# Drone_v1_0.net
KiCad netlist of a schematic drawn in Altium Designer
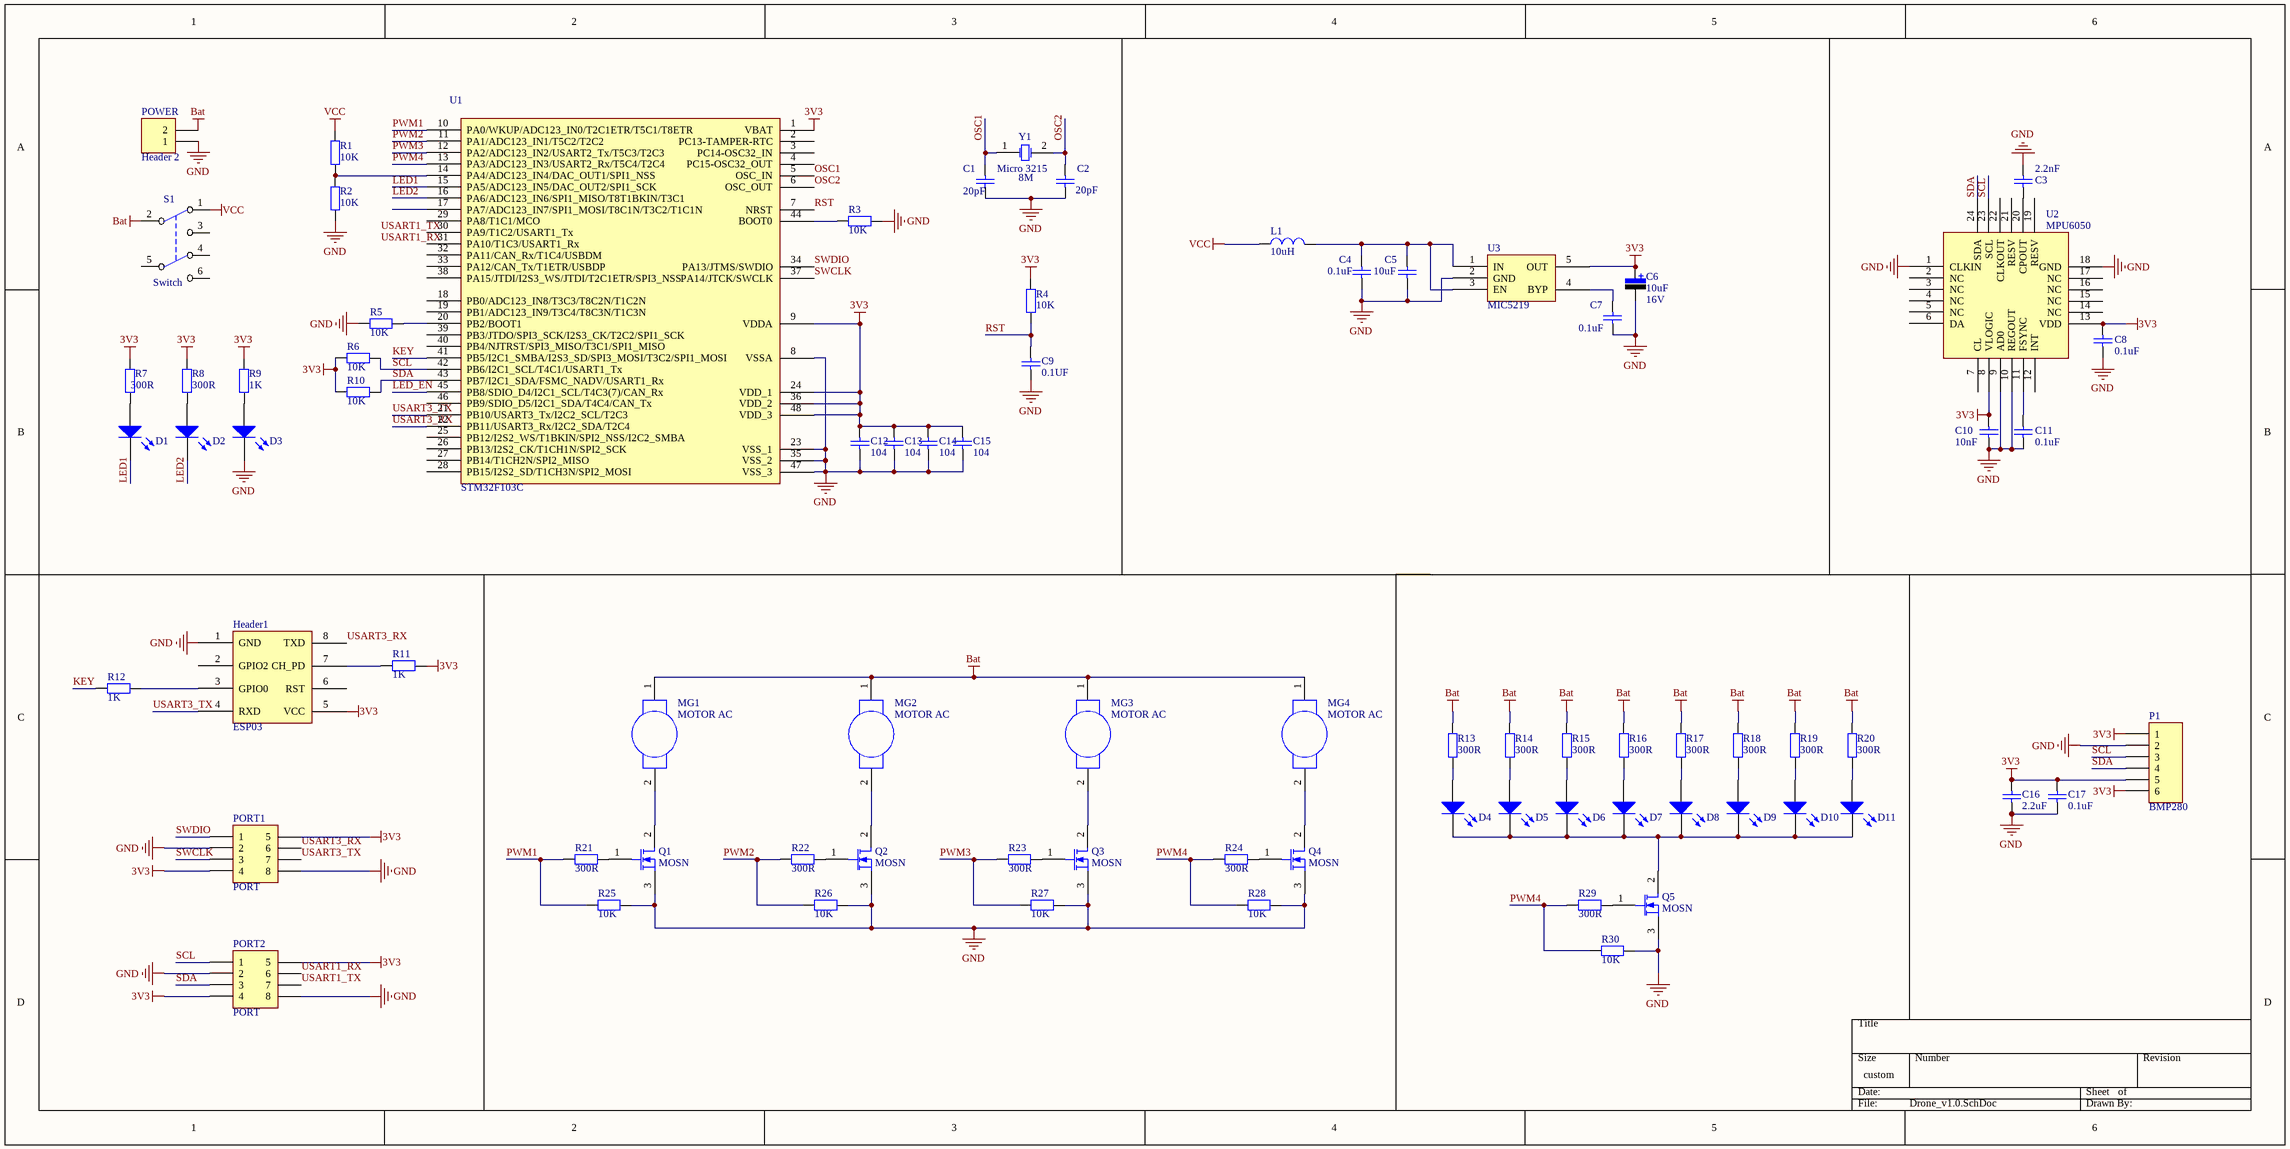
[diagram p0: Drone_v1.0.SchDoc]

(export (version "E")
  (design (tool "Eeschema 10.0.6"))
  (components
    (comp (ref "C1")
      (value "20pF")
      (footprint "0805-2")
      (description "Capacitor")
      (fields (field (name "Comment") "0402 12pF") (field (name "PUBLISHER") "Altium Limited"))
      (libsource (lib "Miscellaneous Devices") (part "Cap"))
    )
    (comp (ref "C2")
      (value "20pF")
      (footprint "0805-2")
      (description "Capacitor")
      (fields (field (name "Comment") "0402 12pF") (field (name "PUBLISHER") "Altium Limited"))
      (libsource (lib "Miscellaneous Devices") (part "Cap"))
    )
    (comp (ref "C3")
      (value "0402 12pF")
      (footprint "0805-2")
      (description "Capacitor")
      (fields (field (name "50V") "2.2nF") (field (name "PUBLISHER") "Altium Limited"))
      (libsource (lib "Miscellaneous Devices") (part "Cap"))
    )
    (comp (ref "C4")
      (value "0.1uF")
      (footprint "0805-2")
      (description "Capacitor")
      (fields (field (name "Comment") "0402 12pF") (field (name "PUBLISHER") "Altium Limited"))
      (libsource (lib "Miscellaneous Devices") (part "Cap"))
    )
    (comp (ref "C5")
      (value "10uF")
      (footprint "0805-2")
      (description "Capacitor")
      (fields (field (name "Comment") "0402 12pF") (field (name "PUBLISHER") "Altium Limited"))
      (libsource (lib "Miscellaneous Devices") (part "Cap"))
    )
    (comp (ref "C6")
      (value "10uF")
      (footprint "1206")
      (description "极性电解电容")
      (fields
        (field (name "VOL") "16V")
        (field (name "Comment") "Cap Pol")
        (field (name "PUBLISHER") "Altium Limited")
      )
      (libsource (lib "Fszhang") (part "Cap Pol"))
    )
    (comp (ref "C7")
      (value "0402 12pF")
      (footprint "0805-2")
      (description "Capacitor")
      (fields (field (name "50V") "0.1uF") (field (name "PUBLISHER") "Altium Limited"))
      (libsource (lib "Miscellaneous Devices") (part "Cap"))
    )
    (comp (ref "C8")
      (value "0402 12pF")
      (footprint "0805-2")
      (description "Capacitor")
      (fields (field (name "50V") "0.1uF") (field (name "PUBLISHER") "Altium Limited"))
      (libsource (lib "Miscellaneous Devices") (part "Cap"))
    )
    (comp (ref "C9")
      (value "0.1UF")
      (footprint "0805-2")
      (description "无极性电容")
      (fields (field (name "Comment") "Cap") (field (name "PUBLISHER") "Altium Limited"))
      (libsource (lib "Fszhang") (part "Cap"))
    )
    (comp (ref "C10")
      (value "0402 12pF")
      (footprint "0805-2")
      (description "Capacitor")
      (fields (field (name "50V") "10nF") (field (name "PUBLISHER") "Altium Limited"))
      (libsource (lib "Miscellaneous Devices") (part "Cap"))
    )
    (comp (ref "C11")
      (value "0402 12pF")
      (footprint "0805-2")
      (description "Capacitor")
      (fields (field (name "50V") "0.1uF") (field (name "PUBLISHER") "Altium Limited"))
      (libsource (lib "Miscellaneous Devices") (part "Cap"))
    )
    (comp (ref "C12")
      (value "104")
      (footprint "0805-2")
      (description "无极性电容")
      (fields (field (name "Comment") "Cap") (field (name "PUBLISHER") "Altium Limited"))
      (libsource (lib "Fszhang") (part "Cap"))
    )
    (comp (ref "C13")
      (value "104")
      (footprint "0805-2")
      (description "无极性电容")
      (fields (field (name "Comment") "Cap") (field (name "PUBLISHER") "Altium Limited"))
      (libsource (lib "Fszhang") (part "Cap"))
    )
    (comp (ref "C14")
      (value "104")
      (footprint "0805-2")
      (description "无极性电容")
      (fields (field (name "Comment") "Cap") (field (name "PUBLISHER") "Altium Limited"))
      (libsource (lib "Fszhang") (part "Cap"))
    )
    (comp (ref "C15")
      (value "104")
      (footprint "0805-2")
      (description "无极性电容")
      (fields (field (name "Comment") "Cap") (field (name "PUBLISHER") "Altium Limited"))
      (libsource (lib "Fszhang") (part "Cap"))
    )
    (comp (ref "C16")
      (value "0402 12pF")
      (footprint "0805-2")
      (description "Capacitor")
      (fields (field (name "50V") "2.2uF") (field (name "PUBLISHER") "Altium Limited"))
      (libsource (lib "Miscellaneous Devices") (part "Cap"))
    )
    (comp (ref "C17")
      (value "0402 12pF")
      (footprint "0805-2")
      (description "Capacitor")
      (fields (field (name "50V") "0.1uF") (field (name "PUBLISHER") "Altium Limited"))
      (libsource (lib "Miscellaneous Devices") (part "Cap"))
    )
    (comp (ref "D1")
      (value "LED0")
      (footprint "LED_0805")
      (description "发光二极管")
      (fields (field (name "PUBLISHER") "Altium Limited"))
      (libsource (lib "Fszhang") (part "LED0"))
    )
    (comp (ref "D2")
      (value "LED0")
      (footprint "LED_0805")
      (description "发光二极管")
      (fields (field (name "PUBLISHER") "Altium Limited"))
      (libsource (lib "Fszhang") (part "LED0"))
    )
    (comp (ref "D3")
      (value "LED0")
      (footprint "LED_0805")
      (description "发光二极管")
      (fields (field (name "PUBLISHER") "Altium Limited"))
      (libsource (lib "Fszhang") (part "LED0"))
    )
    (comp (ref "D4")
      (value "LED0")
      (footprint "LED_0805")
      (description "发光二极管")
      (fields (field (name "PUBLISHER") "Altium Limited"))
      (libsource (lib "Fszhang") (part "LED0"))
    )
    (comp (ref "D5")
      (value "LED0")
      (footprint "LED_0805")
      (description "发光二极管")
      (fields (field (name "PUBLISHER") "Altium Limited"))
      (libsource (lib "Fszhang") (part "LED0"))
    )
    (comp (ref "D6")
      (value "LED0")
      (footprint "LED_0805")
      (description "发光二极管")
      (fields (field (name "PUBLISHER") "Altium Limited"))
      (libsource (lib "Fszhang") (part "LED0"))
    )
    (comp (ref "D7")
      (value "LED0")
      (footprint "LED_0805")
      (description "发光二极管")
      (fields (field (name "PUBLISHER") "Altium Limited"))
      (libsource (lib "Fszhang") (part "LED0"))
    )
    (comp (ref "D8")
      (value "LED0")
      (footprint "LED_0805")
      (description "发光二极管")
      (fields (field (name "PUBLISHER") "Altium Limited"))
      (libsource (lib "Fszhang") (part "LED0"))
    )
    (comp (ref "D9")
      (value "LED0")
      (footprint "LED_0805")
      (description "发光二极管")
      (fields (field (name "PUBLISHER") "Altium Limited"))
      (libsource (lib "Fszhang") (part "LED0"))
    )
    (comp (ref "D10")
      (value "LED0")
      (footprint "LED_0805")
      (description "发光二极管")
      (fields (field (name "PUBLISHER") "Altium Limited"))
      (libsource (lib "Fszhang") (part "LED0"))
    )
    (comp (ref "D11")
      (value "LED0")
      (footprint "LED_0805")
      (description "发光二极管")
      (fields (field (name "PUBLISHER") "Altium Limited"))
      (libsource (lib "Fszhang") (part "LED0"))
    )
    (comp (ref "Header1")
      (value "ESP03")
      (footprint "PCBComponent_1")
      (libsource (lib "Header4") (part "Hearder"))
    )
    (comp (ref "L1")
      (value "10uH")
      (footprint "0805-1")
      (description "电感")
      (fields (field (name "Comment") "Inductor") (field (name "PUBLISHER") "Altium Limited"))
      (libsource (lib "Fszhang") (part "Inductor"))
    )
    (comp (ref "MG1") (value "MOTOR AC") (footprint "Motor") (libsource (lib "杂元件库") (part "MOTOR AC")))
    (comp (ref "MG2") (value "MOTOR AC") (footprint "Motor") (libsource (lib "杂元件库") (part "MOTOR AC")))
    (comp (ref "MG3") (value "MOTOR AC") (footprint "Motor") (libsource (lib "杂元件库") (part "MOTOR AC")))
    (comp (ref "MG4") (value "MOTOR AC") (footprint "Motor") (libsource (lib "杂元件库") (part "MOTOR AC")))
    (comp (ref "P1")
      (value "BMP280")
      (footprint "HDR1X6")
      (description "Header, 6-Pin")
      (fields (field (name "PUBLISHER") "Altium Limited"))
      (libsource (lib "Miscellaneous Connectors") (part "Header 6"))
    )
    (comp (ref "PORT1")
      (value "PORT")
      (footprint "HDR2X4_CEN")
      (description "Header, 4-Pin, Dual row")
      (fields (field (name "PUBLISHER") "Altium Limited"))
      (libsource (lib "Miscellaneous Connectors") (part "Header 4X2A"))
    )
    (comp (ref "PORT2")
      (value "PORT")
      (footprint "HDR2X4_CEN")
      (description "Header, 4-Pin, Dual row")
      (fields (field (name "PUBLISHER") "Altium Limited"))
      (libsource (lib "Miscellaneous Connectors") (part "Header 4X2A"))
    )
    (comp (ref "POWER")
      (value "Header 2")
      (footprint "HDR1X2")
      (description "Header, 2-Pin")
      (fields (field (name "PUBLISHER") "Altium Limited"))
      (libsource (lib "Miscellaneous Connectors") (part "Header 2"))
    )
    (comp (ref "Q1") (value "MOSN") (footprint "PCBComponent_1") (libsource (lib "MOS-N") (part "SI2302")))
    (comp (ref "Q2") (value "MOSN") (footprint "PCBComponent_1") (libsource (lib "MOS-N") (part "SI2302")))
    (comp (ref "Q3") (value "MOSN") (footprint "PCBComponent_1") (libsource (lib "MOS-N") (part "SI2302")))
    (comp (ref "Q4") (value "MOSN") (footprint "PCBComponent_1") (libsource (lib "MOS-N") (part "SI2302")))
    (comp (ref "Q5") (value "MOSN") (footprint "PCBComponent_1") (libsource (lib "MOS-N") (part "SI2302")))
    (comp (ref "R1")
      (value "10K")
      (footprint "0805-2")
      (description "贴片电阻")
      (fields (field (name "Comment") "Res1") (field (name "PUBLISHER") "Altium Limited"))
      (libsource (lib "") (part "Res1_2"))
    )
    (comp (ref "R2")
      (value "10K")
      (footprint "0805-2")
      (description "贴片电阻")
      (fields (field (name "Comment") "Res1") (field (name "PUBLISHER") "Altium Limited"))
      (libsource (lib "") (part "Res1_1"))
    )
    (comp (ref "R3")
      (value "10K")
      (footprint "0805-2")
      (description "贴片电阻")
      (fields (field (name "Comment") "Res1") (field (name "PUBLISHER") "Altium Limited"))
      (libsource (lib "Fszhang") (part "Res1"))
    )
    (comp (ref "R4")
      (value "10K")
      (footprint "0805-2")
      (description "贴片电阻")
      (fields (field (name "Comment") "Res1") (field (name "PUBLISHER") "Altium Limited"))
      (libsource (lib "") (part "Res1_2"))
    )
    (comp (ref "R5")
      (value "10K")
      (footprint "0805-2")
      (description "贴片电阻")
      (fields (field (name "Comment") "Res1") (field (name "PUBLISHER") "Altium Limited"))
      (libsource (lib "") (part "Res1_3"))
    )
    (comp (ref "R6")
      (value "10K")
      (footprint "0805-2")
      (description "贴片电阻")
      (fields (field (name "Comment") "Res1") (field (name "PUBLISHER") "Altium Limited"))
      (libsource (lib "") (part "Res1_3"))
    )
    (comp (ref "R7")
      (value "300R")
      (footprint "0805-2")
      (description "贴片电阻")
      (fields (field (name "Comment") "Res1") (field (name "PUBLISHER") "Altium Limited"))
      (libsource (lib "") (part "Res1_2"))
    )
    (comp (ref "R8")
      (value "300R")
      (footprint "0805-2")
      (description "贴片电阻")
      (fields (field (name "Comment") "Res1") (field (name "PUBLISHER") "Altium Limited"))
      (libsource (lib "") (part "Res1_2"))
    )
    (comp (ref "R9")
      (value "1K")
      (footprint "0805-2")
      (description "贴片电阻")
      (fields (field (name "Comment") "Res1") (field (name "PUBLISHER") "Altium Limited"))
      (libsource (lib "") (part "Res1_2"))
    )
    (comp (ref "R10")
      (value "10K")
      (footprint "0805-2")
      (description "贴片电阻")
      (fields (field (name "Comment") "Res1") (field (name "PUBLISHER") "Altium Limited"))
      (libsource (lib "") (part "Res1_3"))
    )
    (comp (ref "R11")
      (value "1K")
      (footprint "0805-2")
      (description "贴片电阻")
      (fields (field (name "Comment") "Res1") (field (name "PUBLISHER") "Altium Limited"))
      (libsource (lib "") (part "Res1_3"))
    )
    (comp (ref "R12")
      (value "1K")
      (footprint "0805-2")
      (description "贴片电阻")
      (fields (field (name "Comment") "Res1") (field (name "PUBLISHER") "Altium Limited"))
      (libsource (lib "") (part "Res1_3"))
    )
    (comp (ref "R13")
      (value "300R")
      (footprint "0805-2")
      (description "贴片电阻")
      (fields (field (name "Comment") "Res1") (field (name "PUBLISHER") "Altium Limited"))
      (libsource (lib "") (part "Res1_1"))
    )
    (comp (ref "R14")
      (value "300R")
      (footprint "0805-2")
      (description "贴片电阻")
      (fields (field (name "Comment") "Res1") (field (name "PUBLISHER") "Altium Limited"))
      (libsource (lib "") (part "Res1_1"))
    )
    (comp (ref "R15")
      (value "300R")
      (footprint "0805-2")
      (description "贴片电阻")
      (fields (field (name "Comment") "Res1") (field (name "PUBLISHER") "Altium Limited"))
      (libsource (lib "") (part "Res1_1"))
    )
    (comp (ref "R16")
      (value "300R")
      (footprint "0805-2")
      (description "贴片电阻")
      (fields (field (name "Comment") "Res1") (field (name "PUBLISHER") "Altium Limited"))
      (libsource (lib "") (part "Res1_1"))
    )
    (comp (ref "R17")
      (value "300R")
      (footprint "0805-2")
      (description "贴片电阻")
      (fields (field (name "Comment") "Res1") (field (name "PUBLISHER") "Altium Limited"))
      (libsource (lib "") (part "Res1_1"))
    )
    (comp (ref "R18")
      (value "300R")
      (footprint "0805-2")
      (description "贴片电阻")
      (fields (field (name "Comment") "Res1") (field (name "PUBLISHER") "Altium Limited"))
      (libsource (lib "") (part "Res1_1"))
    )
    (comp (ref "R19")
      (value "300R")
      (footprint "0805-2")
      (description "贴片电阻")
      (fields (field (name "Comment") "Res1") (field (name "PUBLISHER") "Altium Limited"))
      (libsource (lib "") (part "Res1_1"))
    )
    (comp (ref "R20")
      (value "300R")
      (footprint "0805-2")
      (description "贴片电阻")
      (fields (field (name "Comment") "Res1") (field (name "PUBLISHER") "Altium Limited"))
      (libsource (lib "") (part "Res1_1"))
    )
    (comp (ref "R21")
      (value "300R")
      (footprint "0805-2")
      (description "贴片电阻")
      (fields (field (name "Comment") "Res1") (field (name "PUBLISHER") "Altium Limited"))
      (libsource (lib "Fszhang") (part "Res1"))
    )
    (comp (ref "R22")
      (value "300R")
      (footprint "0805-2")
      (description "贴片电阻")
      (fields (field (name "Comment") "Res1") (field (name "PUBLISHER") "Altium Limited"))
      (libsource (lib "Fszhang") (part "Res1"))
    )
    (comp (ref "R23")
      (value "300R")
      (footprint "0805-2")
      (description "贴片电阻")
      (fields (field (name "Comment") "Res1") (field (name "PUBLISHER") "Altium Limited"))
      (libsource (lib "Fszhang") (part "Res1"))
    )
    (comp (ref "R24")
      (value "300R")
      (footprint "0805-2")
      (description "贴片电阻")
      (fields (field (name "Comment") "Res1") (field (name "PUBLISHER") "Altium Limited"))
      (libsource (lib "Fszhang") (part "Res1"))
    )
    (comp (ref "R25")
      (value "10K")
      (footprint "0805-2")
      (description "贴片电阻")
      (fields (field (name "Comment") "Res1") (field (name "PUBLISHER") "Altium Limited"))
      (libsource (lib "Fszhang") (part "Res1"))
    )
    (comp (ref "R26")
      (value "10K")
      (footprint "0805-2")
      (description "贴片电阻")
      (fields (field (name "Comment") "Res1") (field (name "PUBLISHER") "Altium Limited"))
      (libsource (lib "Fszhang") (part "Res1"))
    )
    (comp (ref "R27")
      (value "10K")
      (footprint "0805-2")
      (description "贴片电阻")
      (fields (field (name "Comment") "Res1") (field (name "PUBLISHER") "Altium Limited"))
      (libsource (lib "Fszhang") (part "Res1"))
    )
    (comp (ref "R28")
      (value "10K")
      (footprint "0805-2")
      (description "贴片电阻")
      (fields (field (name "Comment") "Res1") (field (name "PUBLISHER") "Altium Limited"))
      (libsource (lib "Fszhang") (part "Res1"))
    )
    (comp (ref "R29")
      (value "300R")
      (footprint "0805-2")
      (description "贴片电阻")
      (fields (field (name "Comment") "Res1") (field (name "PUBLISHER") "Altium Limited"))
      (libsource (lib "Fszhang") (part "Res1"))
    )
    (comp (ref "R30")
      (value "10K")
      (footprint "0805-2")
      (description "贴片电阻")
      (fields (field (name "Comment") "Res1") (field (name "PUBLISHER") "Altium Limited"))
      (libsource (lib "Fszhang") (part "Res1"))
    )
    (comp (ref "S1") (value "Switch") (footprint "开关") (libsource (lib "开关") (part "双刀双柄开关")))
    (comp (ref "U1")
      (value "STM32F103C")
      (footprint "LQFP-48_M")
      (description "STM32单片机48引脚")
      (libsource (lib "Fszhang") (part "STM32F103C"))
    )
    (comp (ref "U2")
      (value "MPU6050")
      (footprint "QFN50P400X400X90-24N")
      (libsource (lib "MPU6050") (part "MPU6050"))
    )
    (comp (ref "U3") (value "MIC5219") (footprint "SOT25-5") (libsource (lib "MIC5219") (part "MIC5219")))
    (comp (ref "Y1")
      (value "Micro 3215")
      (footprint "XTAL5")
      (description "Crystal Oscillator")
      (fields (field (name "ALTIUM_VALUE") "8M"))
      (libsource (lib "Miscellaneous Devices") (part "XTAL"))
    )
  )
  (nets
    (net (code "1") (name "/KEY") (class "Default")
      (node (ref "R12") (pin "1") (pinfunction "1_1") (pintype "passive"))
      (node (ref "U1") (pin "41") (pinfunction "PB5/I2C1_SMBA/I2S3_SD/SPI3_MOSI/T3C2/SPI1_MOSI_41") (pintype "passive"))
    )
    (net (code "2") (name "/LED1") (class "Default")
      (node (ref "D1") (pin "2") (pinfunction "K_2") (pintype "passive"))
      (node (ref "U1") (pin "15") (pinfunction "PA5/ADC123_IN5/DAC_OUT2/SPI1_SCK_15") (pintype "passive"))
    )
    (net (code "3") (name "/LED2") (class "Default")
      (node (ref "D2") (pin "2") (pinfunction "K_2") (pintype "passive"))
      (node (ref "U1") (pin "16") (pinfunction "PA6/ADC123_IN6/SPI1_MISO/T8T1BKIN/T3C1_16") (pintype "passive"))
    )
    (net (code "4") (name "/LED_EN") (class "Default")
      (node (ref "U1") (pin "45") (pinfunction "PB8/SDIO_D4/I2C1_SCL/T4C3(7)/CAN_Rx_45") (pintype "passive"))
    )
    (net (code "5") (name "/OSC1") (class "Default")
      (node (ref "C1") (pin "1") (pinfunction "1_1") (pintype "passive"))
      (node (ref "U1") (pin "5") (pinfunction "OSC_IN_5") (pintype "passive"))
      (node (ref "Y1") (pin "1") (pinfunction "OSC1_1") (pintype "passive"))
    )
    (net (code "6") (name "/OSC2") (class "Default")
      (node (ref "C2") (pin "2") (pinfunction "2_2") (pintype "passive"))
      (node (ref "U1") (pin "6") (pinfunction "OSC_OUT_6") (pintype "passive"))
      (node (ref "Y1") (pin "2") (pinfunction "OSC2_2") (pintype "passive"))
    )
    (net (code "7") (name "/PWM1") (class "Default")
      (node (ref "R21") (pin "2") (pinfunction "2_2") (pintype "passive"))
      (node (ref "R25") (pin "2") (pinfunction "2_2") (pintype "passive"))
      (node (ref "U1") (pin "10") (pinfunction "PA0/WKUP/ADC123_IN0/T2C1ETR/T5C1/T8ETR_10") (pintype "passive"))
    )
    (net (code "8") (name "/PWM2") (class "Default")
      (node (ref "R22") (pin "2") (pinfunction "2_2") (pintype "passive"))
      (node (ref "R26") (pin "2") (pinfunction "2_2") (pintype "passive"))
      (node (ref "U1") (pin "11") (pinfunction "PA1/ADC123_IN1/T5C2/T2C2_11") (pintype "passive"))
    )
    (net (code "9") (name "/PWM3") (class "Default")
      (node (ref "R23") (pin "2") (pinfunction "2_2") (pintype "passive"))
      (node (ref "R27") (pin "2") (pinfunction "2_2") (pintype "passive"))
      (node (ref "U1") (pin "12") (pinfunction "PA2/ADC123_IN2/USART2_Tx/T5C3/T2C3_12") (pintype "passive"))
    )
    (net (code "10") (name "/PWM4") (class "Default")
      (node (ref "R24") (pin "2") (pinfunction "2_2") (pintype "passive"))
      (node (ref "R28") (pin "2") (pinfunction "2_2") (pintype "passive"))
      (node (ref "R29") (pin "2") (pinfunction "2_2") (pintype "passive"))
      (node (ref "R30") (pin "2") (pinfunction "2_2") (pintype "passive"))
      (node (ref "U1") (pin "13") (pinfunction "PA3/ADC123_IN3/USART2_Rx/T5C4/T2C4_13") (pintype "passive"))
    )
    (net (code "11") (name "/RST") (class "Default")
      (node (ref "C9") (pin "1") (pinfunction "1_1") (pintype "passive"))
      (node (ref "R4") (pin "1") (pinfunction "1_1") (pintype "passive"))
      (node (ref "U1") (pin "7") (pinfunction "NRST_7") (pintype "passive"))
    )
    (net (code "12") (name "/SCL") (class "Default")
      (node (ref "P1") (pin "3") (pinfunction "3_3") (pintype "passive"))
      (node (ref "PORT2") (pin "1") (pinfunction "1_1") (pintype "passive"))
      (node (ref "R6") (pin "2") (pinfunction "2_2") (pintype "passive"))
      (node (ref "U1") (pin "42") (pinfunction "PB6/I2C1_SCL/T4C1/USART1_Tx_42") (pintype "passive"))
      (node (ref "U2") (pin "23") (pinfunction "SCL_23") (pintype "passive"))
    )
    (net (code "13") (name "/SDA") (class "Default")
      (node (ref "P1") (pin "4") (pinfunction "4_4") (pintype "passive"))
      (node (ref "PORT2") (pin "3") (pinfunction "3_3") (pintype "passive"))
      (node (ref "R10") (pin "2") (pinfunction "2_2") (pintype "passive"))
      (node (ref "U1") (pin "43") (pinfunction "PB7/I2C1_SDA/FSMC_NADV/USART1_Rx_43") (pintype "passive"))
      (node (ref "U2") (pin "24") (pinfunction "SDA_24") (pintype "passive"))
    )
    (net (code "14") (name "/SWCLK") (class "Default")
      (node (ref "PORT1") (pin "3") (pinfunction "3_3") (pintype "passive"))
      (node (ref "U1") (pin "37") (pinfunction "PA14/JTCK/SWCLK_37") (pintype "passive"))
    )
    (net (code "15") (name "/SWDIO") (class "Default")
      (node (ref "PORT1") (pin "1") (pinfunction "1_1") (pintype "passive"))
      (node (ref "U1") (pin "34") (pinfunction "PA13/JTMS/SWDIO_34") (pintype "passive"))
    )
    (net (code "16") (name "/USART1_RX") (class "Default")
      (node (ref "PORT2") (pin "6") (pinfunction "6_6") (pintype "passive"))
    )
    (net (code "17") (name "/USART1_TX") (class "Default")
      (node (ref "PORT2") (pin "7") (pinfunction "7_7") (pintype "passive"))
    )
    (net (code "18") (name "/USART3_RX") (class "Default")
      (node (ref "Header1") (pin "8") (pinfunction "TXD_8") (pintype "passive"))
      (node (ref "PORT1") (pin "6") (pinfunction "6_6") (pintype "passive"))
      (node (ref "U1") (pin "22") (pinfunction "PB11/USART3_Rx/I2C2_SDA/T2C4_22") (pintype "passive"))
    )
    (net (code "19") (name "/USART3_TX") (class "Default")
      (node (ref "Header1") (pin "4") (pinfunction "RXD_4") (pintype "passive"))
      (node (ref "PORT1") (pin "7") (pinfunction "7_7") (pintype "passive"))
      (node (ref "U1") (pin "21") (pinfunction "PB10/USART3_Tx/I2C2_SCL/T2C3_21") (pintype "passive"))
    )
    (net (code "20") (name "3V3") (class "Default")
      (node (ref "C10") (pin "1") (pinfunction "1_1") (pintype "passive"))
      (node (ref "C12") (pin "2") (pinfunction "2_2") (pintype "passive"))
      (node (ref "C13") (pin "2") (pinfunction "2_2") (pintype "passive"))
      (node (ref "C14") (pin "2") (pinfunction "2_2") (pintype "passive"))
      (node (ref "C15") (pin "2") (pinfunction "2_2") (pintype "passive"))
      (node (ref "C16") (pin "1") (pinfunction "1_1") (pintype "passive"))
      (node (ref "C17") (pin "1") (pinfunction "1_1") (pintype "passive"))
      (node (ref "C6") (pin "1") (pinfunction "1_1") (pintype "passive"))
      (node (ref "C8") (pin "1") (pinfunction "1_1") (pintype "passive"))
      (node (ref "Header1") (pin "5") (pinfunction "VCC_5") (pintype "passive"))
      (node (ref "P1") (pin "1") (pinfunction "1_1") (pintype "passive"))
      (node (ref "P1") (pin "5") (pinfunction "5_5") (pintype "passive"))
      (node (ref "P1") (pin "6") (pinfunction "6_6") (pintype "passive"))
      (node (ref "PORT1") (pin "4") (pinfunction "4_4") (pintype "passive"))
      (node (ref "PORT1") (pin "5") (pinfunction "5_5") (pintype "passive"))
      (node (ref "PORT2") (pin "4") (pinfunction "4_4") (pintype "passive"))
      (node (ref "PORT2") (pin "5") (pinfunction "5_5") (pintype "passive"))
      (node (ref "R10") (pin "1") (pinfunction "1_1") (pintype "passive"))
      (node (ref "R11") (pin "2") (pinfunction "2_2") (pintype "passive"))
      (node (ref "R4") (pin "2") (pinfunction "2_2") (pintype "passive"))
      (node (ref "R6") (pin "1") (pinfunction "1_1") (pintype "passive"))
      (node (ref "R7") (pin "2") (pinfunction "2_2") (pintype "passive"))
      (node (ref "R8") (pin "2") (pinfunction "2_2") (pintype "passive"))
      (node (ref "R9") (pin "2") (pinfunction "2_2") (pintype "passive"))
      (node (ref "U1") (pin "1") (pinfunction "VBAT_1") (pintype "passive"))
      (node (ref "U1") (pin "24") (pinfunction "VDD_1_24") (pintype "passive"))
      (node (ref "U1") (pin "36") (pinfunction "VDD_2_36") (pintype "passive"))
      (node (ref "U1") (pin "48") (pinfunction "VDD_3_48") (pintype "passive"))
      (node (ref "U1") (pin "9") (pinfunction "VDDA_9") (pintype "passive"))
      (node (ref "U2") (pin "13") (pinfunction "VDD_13") (pintype "passive"))
      (node (ref "U2") (pin "8") (pinfunction "VLOGIC_8") (pintype "passive"))
      (node (ref "U3") (pin "5") (pinfunction "OUT_5") (pintype "passive"))
    )
    (net (code "21") (name "Bat") (class "Default")
      (node (ref "MG1") (pin "1") (pinfunction "1_1") (pintype "passive"))
      (node (ref "MG2") (pin "1") (pinfunction "1_1") (pintype "passive"))
      (node (ref "MG3") (pin "1") (pinfunction "1_1") (pintype "passive"))
      (node (ref "MG4") (pin "1") (pinfunction "1_1") (pintype "passive"))
      (node (ref "POWER") (pin "2") (pinfunction "2_2") (pintype "passive"))
      (node (ref "R13") (pin "1") (pinfunction "1_1") (pintype "passive"))
      (node (ref "R14") (pin "1") (pinfunction "1_1") (pintype "passive"))
      (node (ref "R15") (pin "1") (pinfunction "1_1") (pintype "passive"))
      (node (ref "R16") (pin "1") (pinfunction "1_1") (pintype "passive"))
      (node (ref "R17") (pin "1") (pinfunction "1_1") (pintype "passive"))
      (node (ref "R18") (pin "1") (pinfunction "1_1") (pintype "passive"))
      (node (ref "R19") (pin "1") (pinfunction "1_1") (pintype "passive"))
      (node (ref "R20") (pin "1") (pinfunction "1_1") (pintype "passive"))
      (node (ref "S1") (pin "2") (pinfunction "COMMON1_2") (pintype "passive"))
    )
    (net (code "22") (name "GND") (class "Default")
      (node (ref "C1") (pin "2") (pinfunction "2_2") (pintype "passive"))
      (node (ref "C10") (pin "2") (pinfunction "2_2") (pintype "passive"))
      (node (ref "C11") (pin "2") (pinfunction "2_2") (pintype "passive"))
      (node (ref "C12") (pin "1") (pinfunction "1_1") (pintype "passive"))
      (node (ref "C13") (pin "1") (pinfunction "1_1") (pintype "passive"))
      (node (ref "C14") (pin "1") (pinfunction "1_1") (pintype "passive"))
      (node (ref "C15") (pin "1") (pinfunction "1_1") (pintype "passive"))
      (node (ref "C16") (pin "2") (pinfunction "2_2") (pintype "passive"))
      (node (ref "C17") (pin "2") (pinfunction "2_2") (pintype "passive"))
      (node (ref "C2") (pin "1") (pinfunction "1_1") (pintype "passive"))
      (node (ref "C3") (pin "1") (pinfunction "1_1") (pintype "passive"))
      (node (ref "C4") (pin "2") (pinfunction "2_2") (pintype "passive"))
      (node (ref "C5") (pin "2") (pinfunction "2_2") (pintype "passive"))
      (node (ref "C6") (pin "2") (pinfunction "2_2") (pintype "passive"))
      (node (ref "C7") (pin "2") (pinfunction "2_2") (pintype "passive"))
      (node (ref "C8") (pin "2") (pinfunction "2_2") (pintype "passive"))
      (node (ref "C9") (pin "2") (pinfunction "2_2") (pintype "passive"))
      (node (ref "D3") (pin "2") (pinfunction "K_2") (pintype "passive"))
      (node (ref "Header1") (pin "1") (pinfunction "GND_1") (pintype "passive"))
      (node (ref "P1") (pin "2") (pinfunction "2_2") (pintype "passive"))
      (node (ref "PORT1") (pin "2") (pinfunction "2_2") (pintype "passive"))
      (node (ref "PORT1") (pin "8") (pinfunction "8_8") (pintype "passive"))
      (node (ref "PORT2") (pin "2") (pinfunction "2_2") (pintype "passive"))
      (node (ref "PORT2") (pin "8") (pinfunction "8_8") (pintype "passive"))
      (node (ref "POWER") (pin "1") (pinfunction "1_1") (pintype "passive"))
      (node (ref "Q1") (pin "3") (pinfunction "D_3") (pintype "passive"))
      (node (ref "Q2") (pin "3") (pinfunction "D_3") (pintype "passive"))
      (node (ref "Q3") (pin "3") (pinfunction "D_3") (pintype "passive"))
      (node (ref "Q4") (pin "3") (pinfunction "D_3") (pintype "passive"))
      (node (ref "Q5") (pin "3") (pinfunction "D_3") (pintype "passive"))
      (node (ref "R2") (pin "2") (pinfunction "2_2") (pintype "passive"))
      (node (ref "R25") (pin "1") (pinfunction "1_1") (pintype "passive"))
      (node (ref "R26") (pin "1") (pinfunction "1_1") (pintype "passive"))
      (node (ref "R27") (pin "1") (pinfunction "1_1") (pintype "passive"))
      (node (ref "R28") (pin "1") (pinfunction "1_1") (pintype "passive"))
      (node (ref "R3") (pin "1") (pinfunction "1_1") (pintype "passive"))
      (node (ref "R30") (pin "1") (pinfunction "1_1") (pintype "passive"))
      (node (ref "R5") (pin "1") (pinfunction "1_1") (pintype "passive"))
      (node (ref "U1") (pin "23") (pinfunction "VSS_1_23") (pintype "passive"))
      (node (ref "U1") (pin "35") (pinfunction "VSS_2_35") (pintype "passive"))
      (node (ref "U1") (pin "47") (pinfunction "VSS_3_47") (pintype "passive"))
      (node (ref "U1") (pin "8") (pinfunction "VSSA_8") (pintype "passive"))
      (node (ref "U2") (pin "1") (pinfunction "CLKIN_1") (pintype "passive"))
      (node (ref "U2") (pin "10") (pinfunction "REGOUT_10") (pintype "passive"))
      (node (ref "U2") (pin "18") (pinfunction "GND_18") (pintype "passive"))
      (node (ref "U2") (pin "9") (pinfunction "AD0_9") (pintype "passive"))
      (node (ref "U3") (pin "2") (pinfunction "GND_2") (pintype "passive"))
    )
    (net (code "23") (name "Net-(D1-A)") (class "Default")
      (node (ref "D1") (pin "1") (pinfunction "A_1") (pintype "passive"))
      (node (ref "R7") (pin "1") (pinfunction "1_1") (pintype "passive"))
    )
    (net (code "24") (name "Net-(D2-A)") (class "Default")
      (node (ref "D2") (pin "1") (pinfunction "A_1") (pintype "passive"))
      (node (ref "R8") (pin "1") (pinfunction "1_1") (pintype "passive"))
    )
    (net (code "25") (name "Net-(D3-A)") (class "Default")
      (node (ref "D3") (pin "1") (pinfunction "A_1") (pintype "passive"))
      (node (ref "R9") (pin "1") (pinfunction "1_1") (pintype "passive"))
    )
    (net (code "26") (name "Net-(D4-A)") (class "Default")
      (node (ref "D4") (pin "1") (pinfunction "A_1") (pintype "passive"))
      (node (ref "R13") (pin "2") (pinfunction "2_2") (pintype "passive"))
    )
    (net (code "27") (name "Net-(D5-A)") (class "Default")
      (node (ref "D5") (pin "1") (pinfunction "A_1") (pintype "passive"))
      (node (ref "R14") (pin "2") (pinfunction "2_2") (pintype "passive"))
    )
    (net (code "28") (name "Net-(D6-A)") (class "Default")
      (node (ref "D6") (pin "1") (pinfunction "A_1") (pintype "passive"))
      (node (ref "R15") (pin "2") (pinfunction "2_2") (pintype "passive"))
    )
    (net (code "29") (name "Net-(D7-A)") (class "Default")
      (node (ref "D7") (pin "1") (pinfunction "A_1") (pintype "passive"))
      (node (ref "R16") (pin "2") (pinfunction "2_2") (pintype "passive"))
    )
    (net (code "30") (name "Net-(D8-A)") (class "Default")
      (node (ref "D8") (pin "1") (pinfunction "A_1") (pintype "passive"))
      (node (ref "R17") (pin "2") (pinfunction "2_2") (pintype "passive"))
    )
    (net (code "31") (name "Net-(D9-A)") (class "Default")
      (node (ref "D9") (pin "1") (pinfunction "A_1") (pintype "passive"))
      (node (ref "R18") (pin "2") (pinfunction "2_2") (pintype "passive"))
    )
    (net (code "32") (name "Net-(D10-A)") (class "Default")
      (node (ref "D10") (pin "1") (pinfunction "A_1") (pintype "passive"))
      (node (ref "R19") (pin "2") (pinfunction "2_2") (pintype "passive"))
    )
    (net (code "33") (name "Net-(D10-K)") (class "Default")
      (node (ref "D10") (pin "2") (pinfunction "K_2") (pintype "passive"))
      (node (ref "D11") (pin "2") (pinfunction "K_2") (pintype "passive"))
      (node (ref "D4") (pin "2") (pinfunction "K_2") (pintype "passive"))
      (node (ref "D5") (pin "2") (pinfunction "K_2") (pintype "passive"))
      (node (ref "D6") (pin "2") (pinfunction "K_2") (pintype "passive"))
      (node (ref "D7") (pin "2") (pinfunction "K_2") (pintype "passive"))
      (node (ref "D8") (pin "2") (pinfunction "K_2") (pintype "passive"))
      (node (ref "D9") (pin "2") (pinfunction "K_2") (pintype "passive"))
      (node (ref "Q5") (pin "2") (pinfunction "S_2") (pintype "passive"))
    )
    (net (code "34") (name "Net-(D11-A)") (class "Default")
      (node (ref "D11") (pin "1") (pinfunction "A_1") (pintype "passive"))
      (node (ref "R20") (pin "2") (pinfunction "2_2") (pintype "passive"))
    )
    (net (code "35") (name "Net-(Header1-CH_PD)") (class "Default")
      (node (ref "Header1") (pin "7") (pinfunction "CH_PD_7") (pintype "passive"))
      (node (ref "R11") (pin "1") (pinfunction "1_1") (pintype "passive"))
    )
    (net (code "36") (name "Net-(Header1-GPIO0)") (class "Default")
      (node (ref "Header1") (pin "3") (pinfunction "GPIO0_3") (pintype "passive"))
      (node (ref "R12") (pin "2") (pinfunction "2_2") (pintype "passive"))
    )
    (net (code "37") (name "Net-(Q1-G)") (class "Default")
      (node (ref "Q1") (pin "1") (pinfunction "G_1") (pintype "passive"))
      (node (ref "R21") (pin "1") (pinfunction "1_1") (pintype "passive"))
    )
    (net (code "38") (name "Net-(Q1-S)") (class "Default")
      (node (ref "MG1") (pin "2") (pinfunction "2_2") (pintype "passive"))
      (node (ref "Q1") (pin "2") (pinfunction "S_2") (pintype "passive"))
    )
    (net (code "39") (name "Net-(Q2-G)") (class "Default")
      (node (ref "Q2") (pin "1") (pinfunction "G_1") (pintype "passive"))
      (node (ref "R22") (pin "1") (pinfunction "1_1") (pintype "passive"))
    )
    (net (code "40") (name "Net-(Q2-S)") (class "Default")
      (node (ref "MG2") (pin "2") (pinfunction "2_2") (pintype "passive"))
      (node (ref "Q2") (pin "2") (pinfunction "S_2") (pintype "passive"))
    )
    (net (code "41") (name "Net-(Q3-G)") (class "Default")
      (node (ref "Q3") (pin "1") (pinfunction "G_1") (pintype "passive"))
      (node (ref "R23") (pin "1") (pinfunction "1_1") (pintype "passive"))
    )
    (net (code "42") (name "Net-(Q3-S)") (class "Default")
      (node (ref "MG3") (pin "2") (pinfunction "2_2") (pintype "passive"))
      (node (ref "Q3") (pin "2") (pinfunction "S_2") (pintype "passive"))
    )
    (net (code "43") (name "Net-(Q4-G)") (class "Default")
      (node (ref "Q4") (pin "1") (pinfunction "G_1") (pintype "passive"))
      (node (ref "R24") (pin "1") (pinfunction "1_1") (pintype "passive"))
    )
    (net (code "44") (name "Net-(Q4-S)") (class "Default")
      (node (ref "MG4") (pin "2") (pinfunction "2_2") (pintype "passive"))
      (node (ref "Q4") (pin "2") (pinfunction "S_2") (pintype "passive"))
    )
    (net (code "45") (name "Net-(Q5-G)") (class "Default")
      (node (ref "Q5") (pin "1") (pinfunction "G_1") (pintype "passive"))
      (node (ref "R29") (pin "1") (pinfunction "1_1") (pintype "passive"))
    )
    (net (code "46") (name "Net-(U1-BOOT0)") (class "Default")
      (node (ref "R3") (pin "2") (pinfunction "2_2") (pintype "passive"))
      (node (ref "U1") (pin "44") (pinfunction "BOOT0_44") (pintype "passive"))
    )
    (net (code "47") (name "Net-(U1-PA4{slash}ADC123_IN4{slash}DAC_OUT1{slash}SPI1_NSS)") (class "Default")
      (node (ref "R1") (pin "1") (pinfunction "1_1") (pintype "passive"))
      (node (ref "R2") (pin "1") (pinfunction "1_1") (pintype "passive"))
      (node (ref "U1") (pin "14") (pinfunction "PA4/ADC123_IN4/DAC_OUT1/SPI1_NSS_14") (pintype "passive"))
    )
    (net (code "48") (name "Net-(U1-PB2{slash}BOOT1)") (class "Default")
      (node (ref "R5") (pin "2") (pinfunction "2_2") (pintype "passive"))
      (node (ref "U1") (pin "20") (pinfunction "PB2/BOOT1_20") (pintype "passive"))
    )
    (net (code "49") (name "Net-(U2-CPOUT)") (class "Default")
      (node (ref "C3") (pin "2") (pinfunction "2_2") (pintype "passive"))
      (node (ref "U2") (pin "20") (pinfunction "CPOUT_20") (pintype "passive"))
    )
    (net (code "50") (name "Net-(U2-FSYNC)") (class "Default")
      (node (ref "C11") (pin "1") (pinfunction "1_1") (pintype "passive"))
      (node (ref "U2") (pin "11") (pinfunction "FSYNC_11") (pintype "passive"))
    )
    (net (code "51") (name "Net-(U3-BYP)") (class "Default")
      (node (ref "C7") (pin "1") (pinfunction "1_1") (pintype "passive"))
      (node (ref "U3") (pin "4") (pinfunction "BYP_4") (pintype "passive"))
    )
    (net (code "52") (name "Net-(U3-EN)") (class "Default")
      (node (ref "C4") (pin "1") (pinfunction "1_1") (pintype "passive"))
      (node (ref "C5") (pin "1") (pinfunction "1_1") (pintype "passive"))
      (node (ref "L1") (pin "2") (pinfunction "2_2") (pintype "passive"))
      (node (ref "U3") (pin "1") (pinfunction "IN_1") (pintype "passive"))
      (node (ref "U3") (pin "3") (pinfunction "EN_3") (pintype "passive"))
    )
    (net (code "53") (name "VCC") (class "Default")
      (node (ref "L1") (pin "1") (pinfunction "1_1") (pintype "passive"))
      (node (ref "R1") (pin "2") (pinfunction "2_2") (pintype "passive"))
      (node (ref "S1") (pin "1") (pinfunction "NC1_1") (pintype "passive"))
    )
    (net (code "54") (name "unconnected-(Header1-GPIO2-Pad2)") (class "Default")
      (node (ref "Header1") (pin "2") (pinfunction "GPIO2_2") (pintype "passive"))
    )
    (net (code "55") (name "unconnected-(Header1-RST-Pad6)") (class "Default")
      (node (ref "Header1") (pin "6") (pinfunction "RST_6") (pintype "passive"))
    )
    (net (code "56") (name "unconnected-(S1-COMMON2-Pad5)") (class "Default")
      (node (ref "S1") (pin "5") (pinfunction "COMMON2_5") (pintype "passive"))
    )
    (net (code "57") (name "unconnected-(S1-NC2-Pad4)") (class "Default")
      (node (ref "S1") (pin "4") (pinfunction "NC2_4") (pintype "passive"))
    )
    (net (code "58") (name "unconnected-(S1-NO1-Pad3)") (class "Default")
      (node (ref "S1") (pin "3") (pinfunction "NO1_3") (pintype "passive"))
    )
    (net (code "59") (name "unconnected-(S1-NO2-Pad6)") (class "Default")
      (node (ref "S1") (pin "6") (pinfunction "NO2_6") (pintype "passive"))
    )
    (net (code "60") (name "unconnected-(U1-PA7{slash}ADC123_IN7{slash}SPI1_MOSI{slash}T8C1N{slash}T3C2{slash}T1C1N-Pad17)") (class "Default")
      (node (ref "U1") (pin "17") (pinfunction "PA7/ADC123_IN7/SPI1_MOSI/T8C1N/T3C2/T1C1N_17") (pintype "passive"))
    )
    (net (code "61") (name "unconnected-(U1-PA8{slash}T1C1{slash}MCO-Pad29)") (class "Default")
      (node (ref "U1") (pin "29") (pinfunction "PA8/T1C1/MCO_29") (pintype "passive"))
    )
    (net (code "62") (name "unconnected-(U1-PA9{slash}T1C2{slash}USART1_Tx-Pad30)") (class "Default")
      (node (ref "U1") (pin "30") (pinfunction "PA9/T1C2/USART1_Tx_30") (pintype "passive"))
    )
    (net (code "63") (name "unconnected-(U1-PA10{slash}T1C3{slash}USART1_Rx-Pad31)") (class "Default")
      (node (ref "U1") (pin "31") (pinfunction "PA10/T1C3/USART1_Rx_31") (pintype "passive"))
    )
    (net (code "64") (name "unconnected-(U1-PA11{slash}CAN_Rx{slash}T1C4{slash}USBDM-Pad32)") (class "Default")
      (node (ref "U1") (pin "32") (pinfunction "PA11/CAN_Rx/T1C4/USBDM_32") (pintype "passive"))
    )
    (net (code "65") (name "unconnected-(U1-PA12{slash}CAN_Tx{slash}T1ETR{slash}USBDP-Pad33)") (class "Default")
      (node (ref "U1") (pin "33") (pinfunction "PA12/CAN_Tx/T1ETR/USBDP_33") (pintype "passive"))
    )
    (net (code "66") (name "unconnected-(U1-PA15{slash}JTDI{slash}I2S3_WS{slash}JTDI{slash}T2C1ETR{slash}SPI3_NSS-Pad38)") (class "Default")
      (node (ref "U1") (pin "38") (pinfunction "PA15/JTDI/I2S3_WS/JTDI/T2C1ETR/SPI3_NSS_38") (pintype "passive"))
    )
    (net (code "67") (name "unconnected-(U1-PB0{slash}ADC123_IN8{slash}T3C3{slash}T8C2N{slash}T1C2N-Pad18)") (class "Default")
      (node (ref "U1") (pin "18") (pinfunction "PB0/ADC123_IN8/T3C3/T8C2N/T1C2N_18") (pintype "passive"))
    )
    (net (code "68") (name "unconnected-(U1-PB1{slash}ADC123_IN9{slash}T3C4{slash}T8C3N{slash}T1C3N-Pad19)") (class "Default")
      (node (ref "U1") (pin "19") (pinfunction "PB1/ADC123_IN9/T3C4/T8C3N/T1C3N_19") (pintype "passive"))
    )
    (net (code "69") (name "unconnected-(U1-PB3{slash}JTDO{slash}SPI3_SCK{slash}I2S3_CK{slash}T2C2{slash}SPI1_SCK-Pad39)") (class "Default")
      (node (ref "U1") (pin "39") (pinfunction "PB3/JTDO/SPI3_SCK/I2S3_CK/T2C2/SPI1_SCK_39") (pintype "passive"))
    )
    (net (code "70") (name "unconnected-(U1-PB4{slash}NJTRST{slash}SPI3_MISO{slash}T3C1{slash}SPI1_MISO-Pad40)") (class "Default")
      (node (ref "U1") (pin "40") (pinfunction "PB4/NJTRST/SPI3_MISO/T3C1/SPI1_MISO_40") (pintype "passive"))
    )
    (net (code "71") (name "unconnected-(U1-PB9{slash}SDIO_D5{slash}I2C1_SDA{slash}T4C4{slash}CAN_Tx-Pad46)") (class "Default")
      (node (ref "U1") (pin "46") (pinfunction "PB9/SDIO_D5/I2C1_SDA/T4C4/CAN_Tx_46") (pintype "passive"))
    )
    (net (code "72") (name "unconnected-(U1-PB12{slash}I2S2_WS{slash}T1BKIN{slash}SPI2_NSS{slash}I2C2_SMBA-Pad25)") (class "Default")
      (node (ref "U1") (pin "25") (pinfunction "PB12/I2S2_WS/T1BKIN/SPI2_NSS/I2C2_SMBA_25") (pintype "passive"))
    )
    (net (code "73") (name "unconnected-(U1-PB13{slash}I2S2_CK{slash}T1CH1N{slash}SPI2_SCK-Pad26)") (class "Default")
      (node (ref "U1") (pin "26") (pinfunction "PB13/I2S2_CK/T1CH1N/SPI2_SCK_26") (pintype "passive"))
    )
    (net (code "74") (name "unconnected-(U1-PB14{slash}T1CH2N{slash}SPI2_MISO-Pad27)") (class "Default")
      (node (ref "U1") (pin "27") (pinfunction "PB14/T1CH2N/SPI2_MISO_27") (pintype "passive"))
    )
    (net (code "75") (name "unconnected-(U1-PB15{slash}I2S2_SD{slash}T1CH3N{slash}SPI2_MOSI-Pad28)") (class "Default")
      (node (ref "U1") (pin "28") (pinfunction "PB15/I2S2_SD/T1CH3N/SPI2_MOSI_28") (pintype "passive"))
    )
    (net (code "76") (name "unconnected-(U1-PC13-TAMPER-RTC-Pad2)") (class "Default")
      (node (ref "U1") (pin "2") (pinfunction "PC13-TAMPER-RTC_2") (pintype "passive"))
    )
    (net (code "77") (name "unconnected-(U1-PC14-OSC32_IN-Pad3)") (class "Default")
      (node (ref "U1") (pin "3") (pinfunction "PC14-OSC32_IN_3") (pintype "passive"))
    )
    (net (code "78") (name "unconnected-(U1-PC15-OSC32_OUT-Pad4)") (class "Default")
      (node (ref "U1") (pin "4") (pinfunction "PC15-OSC32_OUT_4") (pintype "passive"))
    )
    (net (code "79") (name "unconnected-(U2-CL-Pad7)") (class "Default")
      (node (ref "U2") (pin "7") (pinfunction "CL_7") (pintype "passive"))
    )
    (net (code "80") (name "unconnected-(U2-CLKOUT-Pad22)") (class "Default")
      (node (ref "U2") (pin "22") (pinfunction "CLKOUT_22") (pintype "passive"))
    )
    (net (code "81") (name "unconnected-(U2-DA-Pad6)") (class "Default")
      (node (ref "U2") (pin "6") (pinfunction "DA_6") (pintype "passive"))
    )
    (net (code "82") (name "unconnected-(U2-INT-Pad12)") (class "Default")
      (node (ref "U2") (pin "12") (pinfunction "INT_12") (pintype "passive"))
    )
    (net (code "83") (name "unconnected-(U2-NC-Pad2)") (class "Default")
      (node (ref "U2") (pin "2") (pinfunction "NC_2") (pintype "passive"))
    )
    (net (code "84") (name "unconnected-(U2-NC-Pad3)") (class "Default")
      (node (ref "U2") (pin "3") (pinfunction "NC_3") (pintype "passive"))
    )
    (net (code "85") (name "unconnected-(U2-NC-Pad4)") (class "Default")
      (node (ref "U2") (pin "4") (pinfunction "NC_4") (pintype "passive"))
    )
    (net (code "86") (name "unconnected-(U2-NC-Pad5)") (class "Default")
      (node (ref "U2") (pin "5") (pinfunction "NC_5") (pintype "passive"))
    )
    (net (code "87") (name "unconnected-(U2-NC-Pad14)") (class "Default")
      (node (ref "U2") (pin "14") (pinfunction "NC_14") (pintype "passive"))
    )
    (net (code "88") (name "unconnected-(U2-NC-Pad15)") (class "Default")
      (node (ref "U2") (pin "15") (pinfunction "NC_15") (pintype "passive"))
    )
    (net (code "89") (name "unconnected-(U2-NC-Pad16)") (class "Default")
      (node (ref "U2") (pin "16") (pinfunction "NC_16") (pintype "passive"))
    )
    (net (code "90") (name "unconnected-(U2-NC-Pad17)") (class "Default")
      (node (ref "U2") (pin "17") (pinfunction "NC_17") (pintype "passive"))
    )
    (net (code "91") (name "unconnected-(U2-RESV-Pad19)") (class "Default")
      (node (ref "U2") (pin "19") (pinfunction "RESV_19") (pintype "passive"))
    )
    (net (code "92") (name "unconnected-(U2-RESV-Pad21)") (class "Default")
      (node (ref "U2") (pin "21") (pinfunction "RESV_21") (pintype "passive"))
    )
  )
)
